# Main.net
KiCad netlist of a schematic drawn in Altium Designer
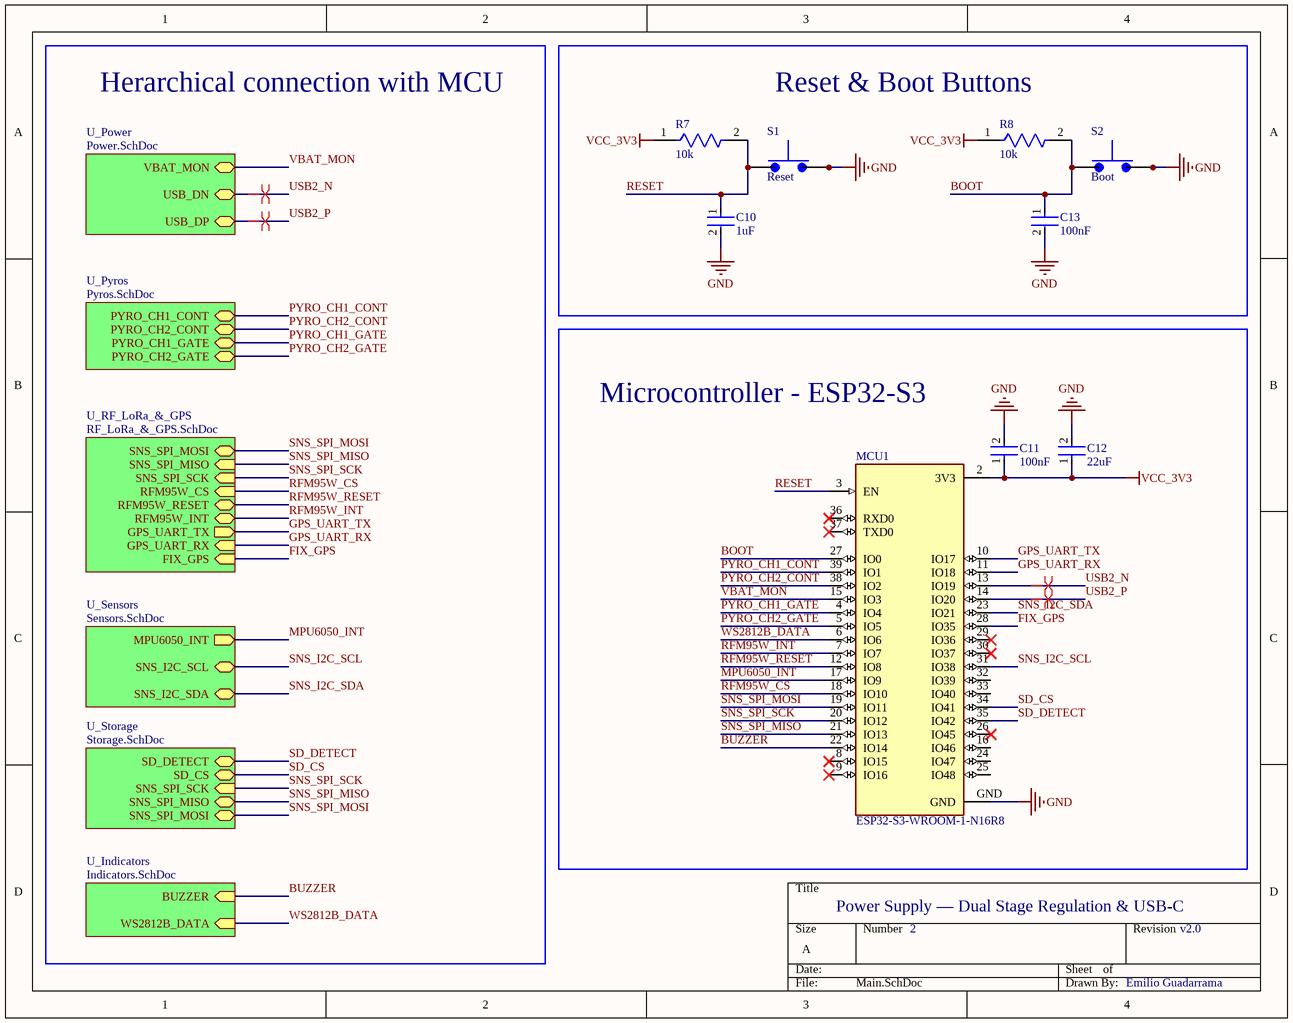
[diagram p0: Main.SchDoc]

(export (version "E")
  (design (tool "Eeschema 10.0.6"))
  (components
    (comp (ref "C10")
      (value "1uF")
      (footprint "FP-C0805C-DN-MFG")
      (description "CAP CER 0.1UF 50V X7R 0805")
      (fields
        (field (name "MANUFACTURER PART NUMBER") "C0805C104K5RACTU")
        (field (name "MANUFACTURER") "KEMET")
      )
      (libsource (lib "Altium Content Vault") (part "b4654b650e69147ec39a6b967a45e02"))
    )
    (comp (ref "C11")
      (value "100nF")
      (footprint "FP-C0805C-DN-MFG")
      (description "CAP CER 0.1UF 50V X7R 0805")
      (fields
        (field (name "MANUFACTURER PART NUMBER") "C0805C104K5RACTU")
        (field (name "MANUFACTURER") "KEMET")
      )
      (libsource (lib "Altium Content Vault") (part "b4654b650e69147ec39a6b967a45e02"))
    )
    (comp (ref "C12")
      (value "22uF")
      (footprint "FP-C0805C-DN-MFG")
      (description "CAP CER 0.1UF 50V X7R 0805")
      (fields
        (field (name "MANUFACTURER PART NUMBER") "C0805C104K5RACTU")
        (field (name "MANUFACTURER") "KEMET")
      )
      (libsource (lib "Altium Content Vault") (part "b4654b650e69147ec39a6b967a45e02"))
    )
    (comp (ref "C13")
      (value "100nF")
      (footprint "FP-C0805C-DN-MFG")
      (description "CAP CER 0.1UF 50V X7R 0805")
      (fields
        (field (name "MANUFACTURER PART NUMBER") "C0805C104K5RACTU")
        (field (name "MANUFACTURER") "KEMET")
      )
      (libsource (lib "Altium Content Vault") (part "b4654b650e69147ec39a6b967a45e02"))
    )
    (comp (ref "MCU1")
      (value "ESP32-S3-WROOM-1-N16R8")
      (footprint "XCVR_ESP32-S3-WROOM-1-N16R2")
      (description "Bluetooth, WiFi 802.11b/g/n, Bluetooth v5.0 Transceiver Module 2.4GHz PCB Trace Surface Mount")
      (fields (field (name "MF") "Espressif Systems") (field (name "MP") "ESP32S3WROOM1N16R2"))
      (libsource (lib "ESP32-S3-WROOM-1-N16R2") (part "ESP32-S3-WROOM-1-N16R2"))
    )
    (comp (ref "R7")
      (value "10k")
      (footprint "FP-MCT0603-IPC_A")
      (description "RES SMD 100 OHM 1% 1/8W 0603")
      (fields (field (name "TOLERANCE") "0.1%"))
      (libsource (lib "Altium Content Vault") (part "1029c3af85768c4190bb7ad29bc67b5"))
    )
    (comp (ref "R8")
      (value "10k")
      (footprint "FP-MCT0603-IPC_A")
      (description "RES SMD 100 OHM 1% 1/8W 0603")
      (fields (field (name "TOLERANCE") "0.1%"))
      (libsource (lib "Altium Content Vault") (part "1029c3af85768c4190bb7ad29bc67b5"))
    )
    (comp (ref "S1")
      (value "Reset")
      (footprint "SW_SKRPABE010")
      (description "Switch Tactile N.O. SPST Button J-Bend 0.05A 16VDC 1.57N SMD Automotive T/R")
      (fields (field (name "MF") "ALPS") (field (name "MP") "SKRPABE010"))
      (libsource (lib "Button-SKRPABE010") (part "SKRPABE010"))
    )
    (comp (ref "S2")
      (value "Boot")
      (footprint "SW_SKRPABE010")
      (description "Switch Tactile N.O. SPST Button J-Bend 0.05A 16VDC 1.57N SMD Automotive T/R")
      (fields (field (name "MF") "ALPS") (field (name "MP") "SKRPABE010"))
      (libsource (lib "Button-SKRPABE010") (part "SKRPABE010"))
    )
  )
  (nets
    (net (code "2") (name "/BOOT") (class "Default")
      (node (ref "C13") (pin "1") (pinfunction "1_1") (pintype "passive"))
      (node (ref "MCU1") (pin "27") (pinfunction "IO0_27") (pintype "bidirectional"))
      (node (ref "R8") (pin "2") (pinfunction "2_2") (pintype "passive"))
      (node (ref "S2") (pin "1") (pinfunction "1_1") (pintype "passive"))
      (node (ref "S2") (pin "2") (pinfunction "1_2") (pintype "passive"))
    )
    (net (code "3") (name "/BUZZER") (class "Default")
      (node (ref "MCU1") (pin "22") (pinfunction "IO14_22") (pintype "bidirectional"))
    )
    (net (code "4") (name "/FIX_GPS") (class "Default")
      (node (ref "MCU1") (pin "28") (pinfunction "IO35_28") (pintype "bidirectional"))
    )
    (net (code "5") (name "/GPS_UART_RX") (class "Default")
      (node (ref "MCU1") (pin "11") (pinfunction "IO18_11") (pintype "bidirectional"))
    )
    (net (code "6") (name "/GPS_UART_TX") (class "Default")
      (node (ref "MCU1") (pin "10") (pinfunction "IO17_10") (pintype "bidirectional"))
    )
    (net (code "7") (name "/MPU6050_INT") (class "Default")
      (node (ref "MCU1") (pin "17") (pinfunction "IO9_17") (pintype "bidirectional"))
    )
    (net (code "8") (name "/PYRO_CH1_CONT") (class "Default")
      (node (ref "MCU1") (pin "39") (pinfunction "IO1_39") (pintype "bidirectional"))
    )
    (net (code "9") (name "/PYRO_CH1_GATE") (class "Default")
      (node (ref "MCU1") (pin "4") (pinfunction "IO4_4") (pintype "bidirectional"))
    )
    (net (code "10") (name "/PYRO_CH2_CONT") (class "Default")
      (node (ref "MCU1") (pin "38") (pinfunction "IO2_38") (pintype "bidirectional"))
    )
    (net (code "11") (name "/PYRO_CH2_GATE") (class "Default")
      (node (ref "MCU1") (pin "5") (pinfunction "IO5_5") (pintype "bidirectional"))
    )
    (net (code "12") (name "/RESET") (class "Default")
      (node (ref "C10") (pin "1") (pinfunction "1_1") (pintype "passive"))
      (node (ref "MCU1") (pin "3") (pinfunction "EN_3") (pintype "input"))
      (node (ref "R7") (pin "2") (pinfunction "2_2") (pintype "passive"))
      (node (ref "S1") (pin "1") (pinfunction "1_1") (pintype "passive"))
      (node (ref "S1") (pin "2") (pinfunction "1_2") (pintype "passive"))
    )
    (net (code "13") (name "/RFM95W_CS") (class "Default")
      (node (ref "MCU1") (pin "18") (pinfunction "IO10_18") (pintype "bidirectional"))
    )
    (net (code "14") (name "/RFM95W_INT") (class "Default")
      (node (ref "MCU1") (pin "7") (pinfunction "IO7_7") (pintype "bidirectional"))
    )
    (net (code "15") (name "/RFM95W_RESET") (class "Default")
      (node (ref "MCU1") (pin "12") (pinfunction "IO8_12") (pintype "bidirectional"))
    )
    (net (code "16") (name "/SD_CS") (class "Default")
      (node (ref "MCU1") (pin "34") (pinfunction "IO41_34") (pintype "bidirectional"))
    )
    (net (code "17") (name "/SD_DETECT") (class "Default")
      (node (ref "MCU1") (pin "35") (pinfunction "IO42_35") (pintype "bidirectional"))
    )
    (net (code "18") (name "/SNS_I2C_SCL") (class "Default")
      (node (ref "MCU1") (pin "31") (pinfunction "IO38_31") (pintype "bidirectional"))
    )
    (net (code "19") (name "/SNS_I2C_SDA") (class "Default")
      (node (ref "MCU1") (pin "23") (pinfunction "IO21_23") (pintype "bidirectional"))
    )
    (net (code "20") (name "/SNS_SPI_MISO") (class "Default")
      (node (ref "MCU1") (pin "21") (pinfunction "IO13_21") (pintype "bidirectional"))
    )
    (net (code "21") (name "/SNS_SPI_MOSI") (class "Default")
      (node (ref "MCU1") (pin "19") (pinfunction "IO11_19") (pintype "bidirectional"))
    )
    (net (code "22") (name "/SNS_SPI_SCK") (class "Default")
      (node (ref "MCU1") (pin "20") (pinfunction "IO12_20") (pintype "bidirectional"))
    )
    (net (code "23") (name "/USB2_N") (class "Default")
      (node (ref "MCU1") (pin "13") (pinfunction "IO19_13") (pintype "bidirectional"))
    )
    (net (code "24") (name "/USB2_P") (class "Default")
      (node (ref "MCU1") (pin "14") (pinfunction "IO20_14") (pintype "bidirectional"))
    )
    (net (code "25") (name "/VBAT_MON") (class "Default")
      (node (ref "MCU1") (pin "15") (pinfunction "IO3_15") (pintype "bidirectional"))
    )
    (net (code "26") (name "/WS2812B_DATA") (class "Default")
      (node (ref "MCU1") (pin "6") (pinfunction "IO6_6") (pintype "bidirectional"))
    )
    (net (code "27") (name "GND") (class "Default")
      (node (ref "C10") (pin "2") (pinfunction "2_2") (pintype "passive"))
      (node (ref "C11") (pin "2") (pinfunction "2_2") (pintype "passive"))
      (node (ref "C12") (pin "2") (pinfunction "2_2") (pintype "passive"))
      (node (ref "C13") (pin "2") (pinfunction "2_2") (pintype "passive"))
      (node (ref "MCU1") (pin "GND") (pinfunction "GND_GND") (pintype "power_in"))
      (node (ref "S1") (pin "3") (pinfunction "2_3") (pintype "passive"))
      (node (ref "S1") (pin "4") (pinfunction "2_4") (pintype "passive"))
      (node (ref "S2") (pin "3") (pinfunction "2_3") (pintype "passive"))
      (node (ref "S2") (pin "4") (pinfunction "2_4") (pintype "passive"))
    )
    (net (code "28") (name "VCC_3V3") (class "Default")
      (node (ref "C11") (pin "1") (pinfunction "1_1") (pintype "passive"))
      (node (ref "C12") (pin "1") (pinfunction "1_1") (pintype "passive"))
      (node (ref "MCU1") (pin "2") (pinfunction "3V3_2") (pintype "power_in"))
      (node (ref "R7") (pin "1") (pinfunction "1_1") (pintype "passive"))
      (node (ref "R8") (pin "1") (pinfunction "1_1") (pintype "passive"))
    )
    (net (code "29") (name "unconnected-(MCU1-IO15-Pad8)") (class "Default")
      (node (ref "MCU1") (pin "8") (pinfunction "IO15_8") (pintype "bidirectional+no_connect"))
    )
    (net (code "30") (name "unconnected-(MCU1-IO16-Pad9)") (class "Default")
      (node (ref "MCU1") (pin "9") (pinfunction "IO16_9") (pintype "bidirectional+no_connect"))
    )
    (net (code "31") (name "unconnected-(MCU1-IO36-Pad29)") (class "Default")
      (node (ref "MCU1") (pin "29") (pinfunction "IO36_29") (pintype "bidirectional+no_connect"))
    )
    (net (code "32") (name "unconnected-(MCU1-IO37-Pad30)") (class "Default")
      (node (ref "MCU1") (pin "30") (pinfunction "IO37_30") (pintype "bidirectional+no_connect"))
    )
    (net (code "33") (name "unconnected-(MCU1-IO39-Pad32)") (class "Default")
      (node (ref "MCU1") (pin "32") (pinfunction "IO39_32") (pintype "bidirectional"))
    )
    (net (code "34") (name "unconnected-(MCU1-IO40-Pad33)") (class "Default")
      (node (ref "MCU1") (pin "33") (pinfunction "IO40_33") (pintype "bidirectional"))
    )
    (net (code "35") (name "unconnected-(MCU1-IO45-Pad26)") (class "Default")
      (node (ref "MCU1") (pin "26") (pinfunction "IO45_26") (pintype "bidirectional+no_connect"))
    )
    (net (code "36") (name "unconnected-(MCU1-IO46-Pad16)") (class "Default")
      (node (ref "MCU1") (pin "16") (pinfunction "IO46_16") (pintype "bidirectional"))
    )
    (net (code "37") (name "unconnected-(MCU1-IO47-Pad24)") (class "Default")
      (node (ref "MCU1") (pin "24") (pinfunction "IO47_24") (pintype "bidirectional"))
    )
    (net (code "38") (name "unconnected-(MCU1-IO48-Pad25)") (class "Default")
      (node (ref "MCU1") (pin "25") (pinfunction "IO48_25") (pintype "bidirectional"))
    )
    (net (code "39") (name "unconnected-(MCU1-RXD0-Pad36)") (class "Default")
      (node (ref "MCU1") (pin "36") (pinfunction "RXD0_36") (pintype "bidirectional+no_connect"))
    )
    (net (code "40") (name "unconnected-(MCU1-TXD0-Pad37)") (class "Default")
      (node (ref "MCU1") (pin "37") (pinfunction "TXD0_37") (pintype "bidirectional+no_connect"))
    )
  )
)
